# S7CAS-PLEIADES-CARTE-MERE_P06_MOTOR.net
KiCad netlist of a schematic drawn in Altium Designer
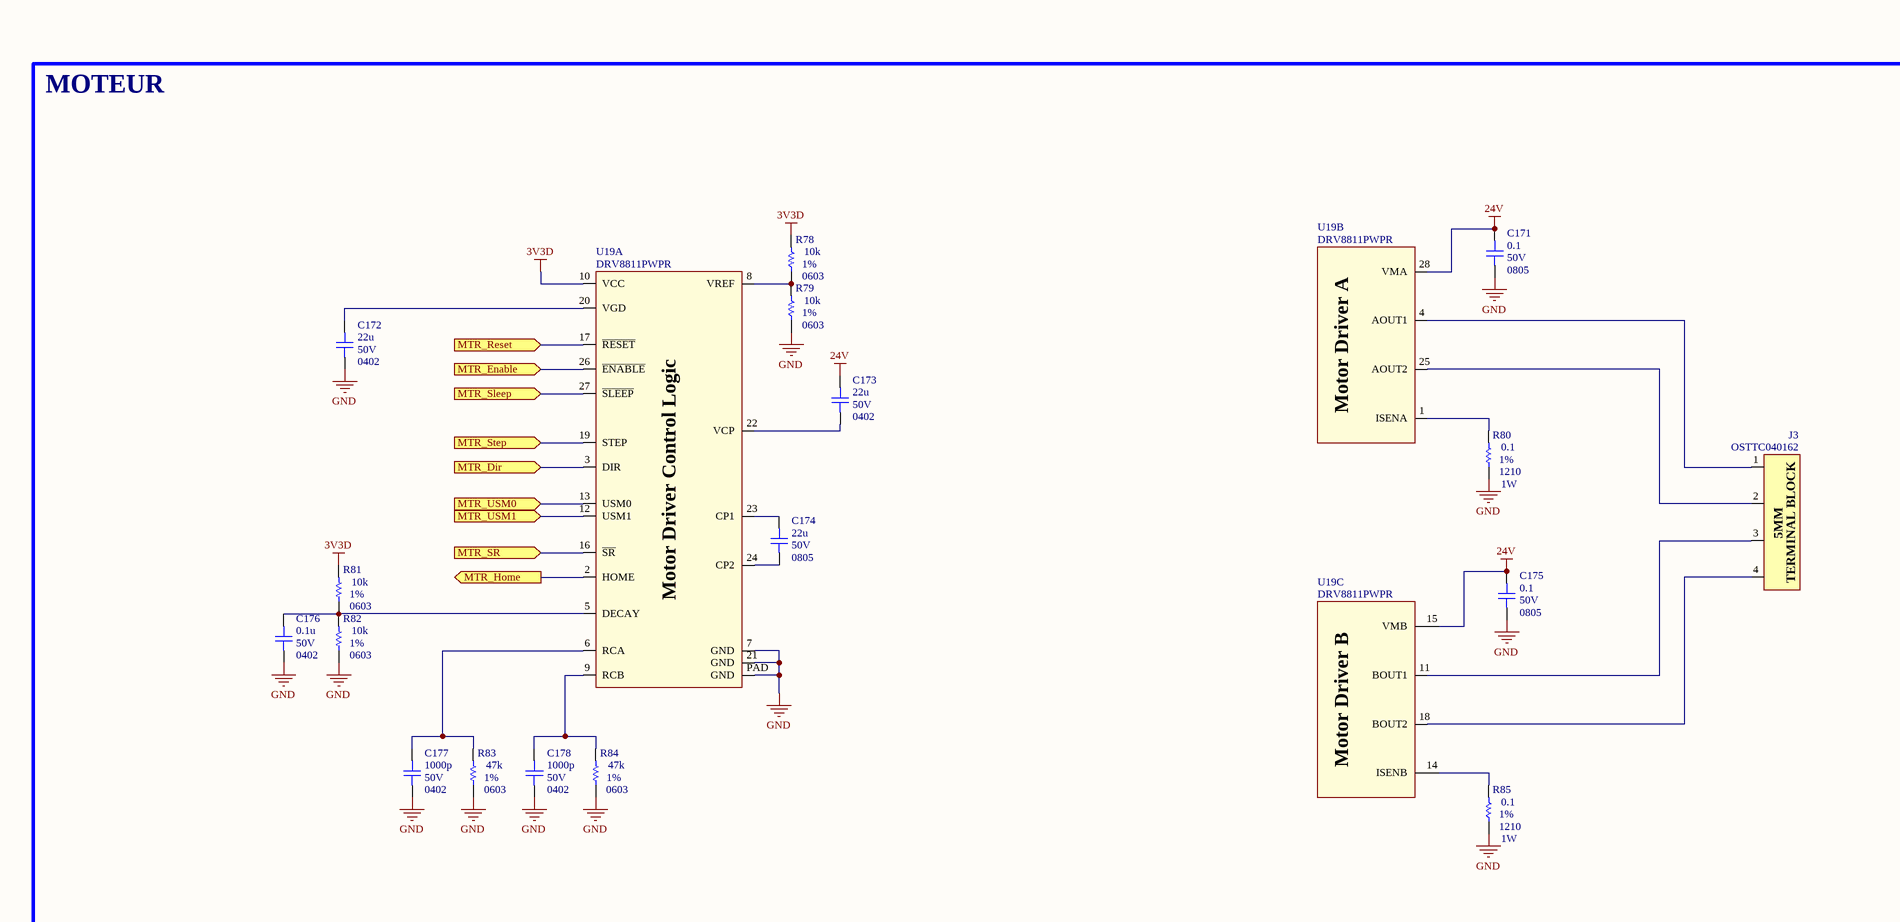
[diagram p0: S7CAS-PLEIADES-CARTE-MERE_P06_MOTOR.SCHDOC, top left]
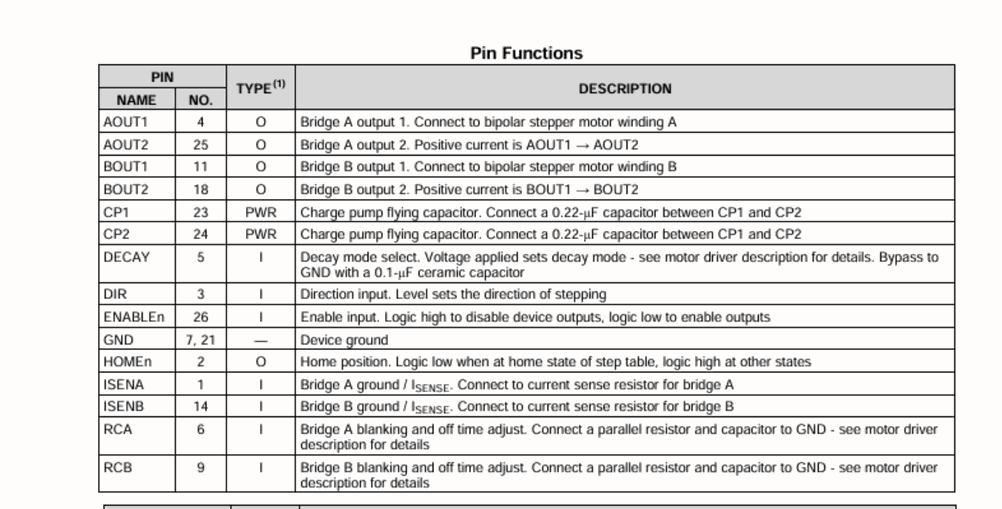
[diagram p1: S7CAS-PLEIADES-CARTE-MERE_P06_MOTOR.SCHDOC, top right]
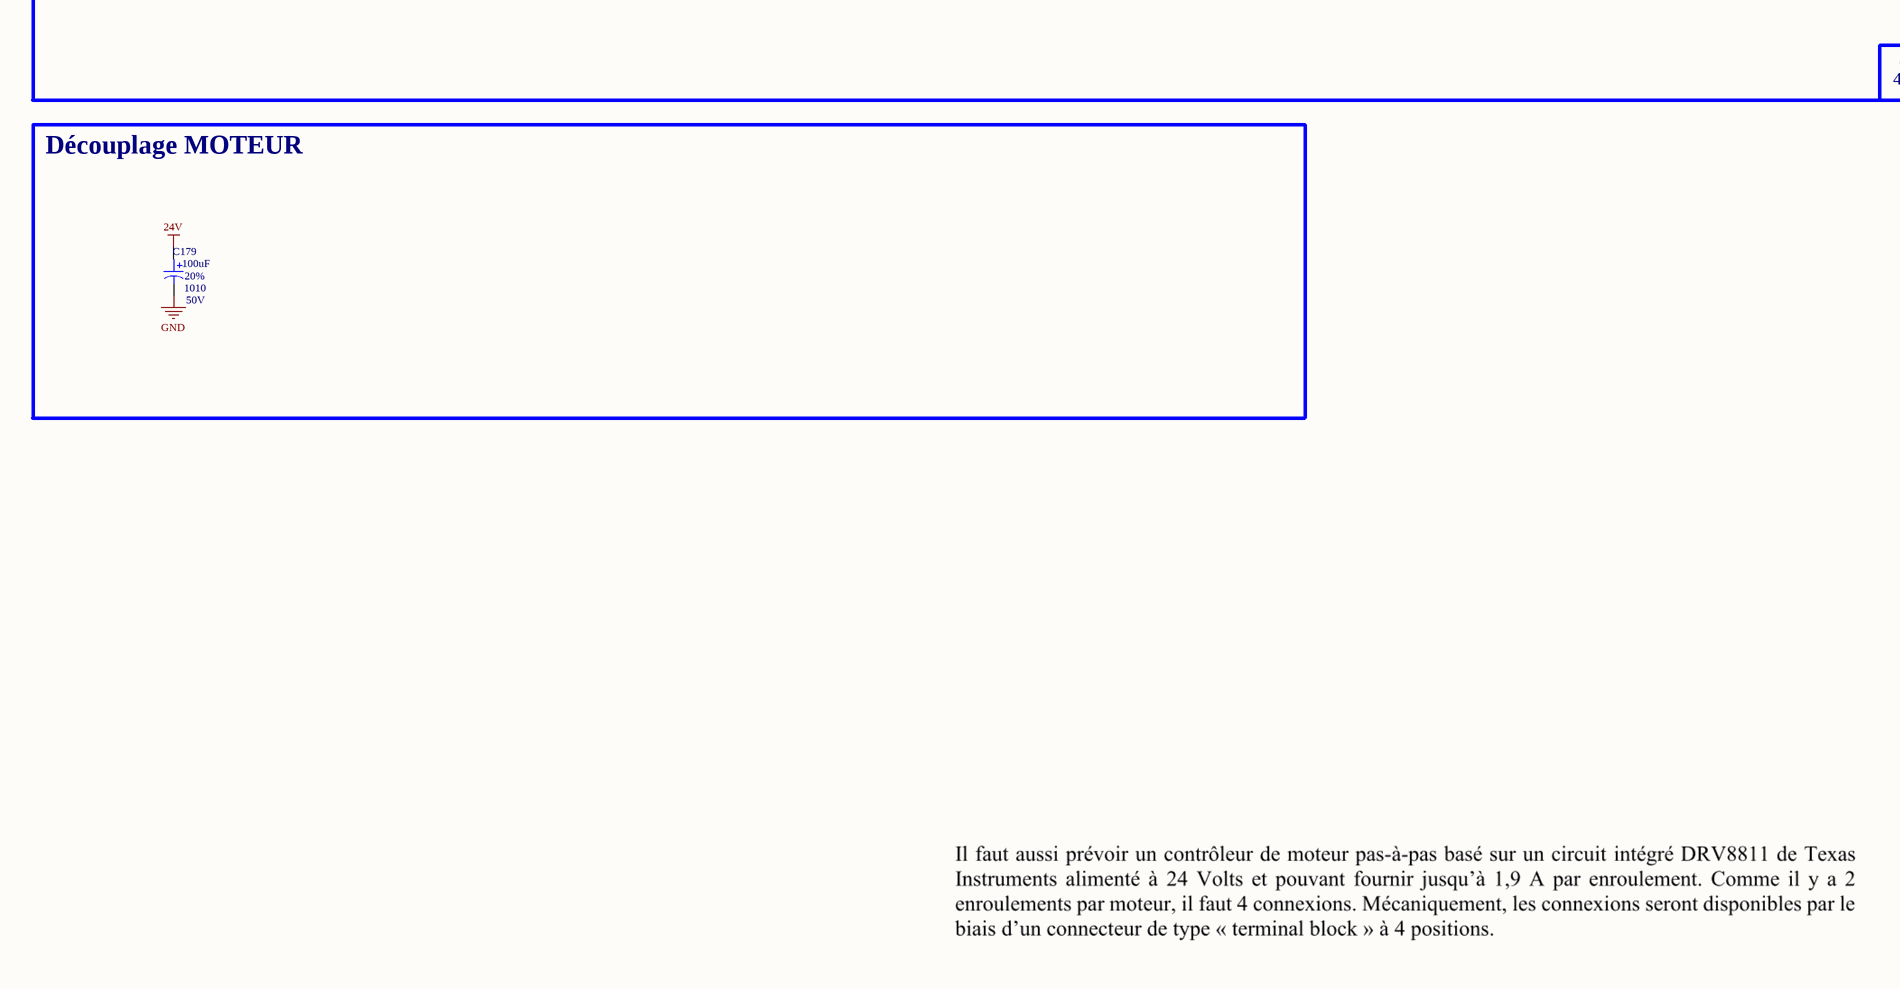
[diagram p2: S7CAS-PLEIADES-CARTE-MERE_P06_MOTOR.SCHDOC, bottom left]
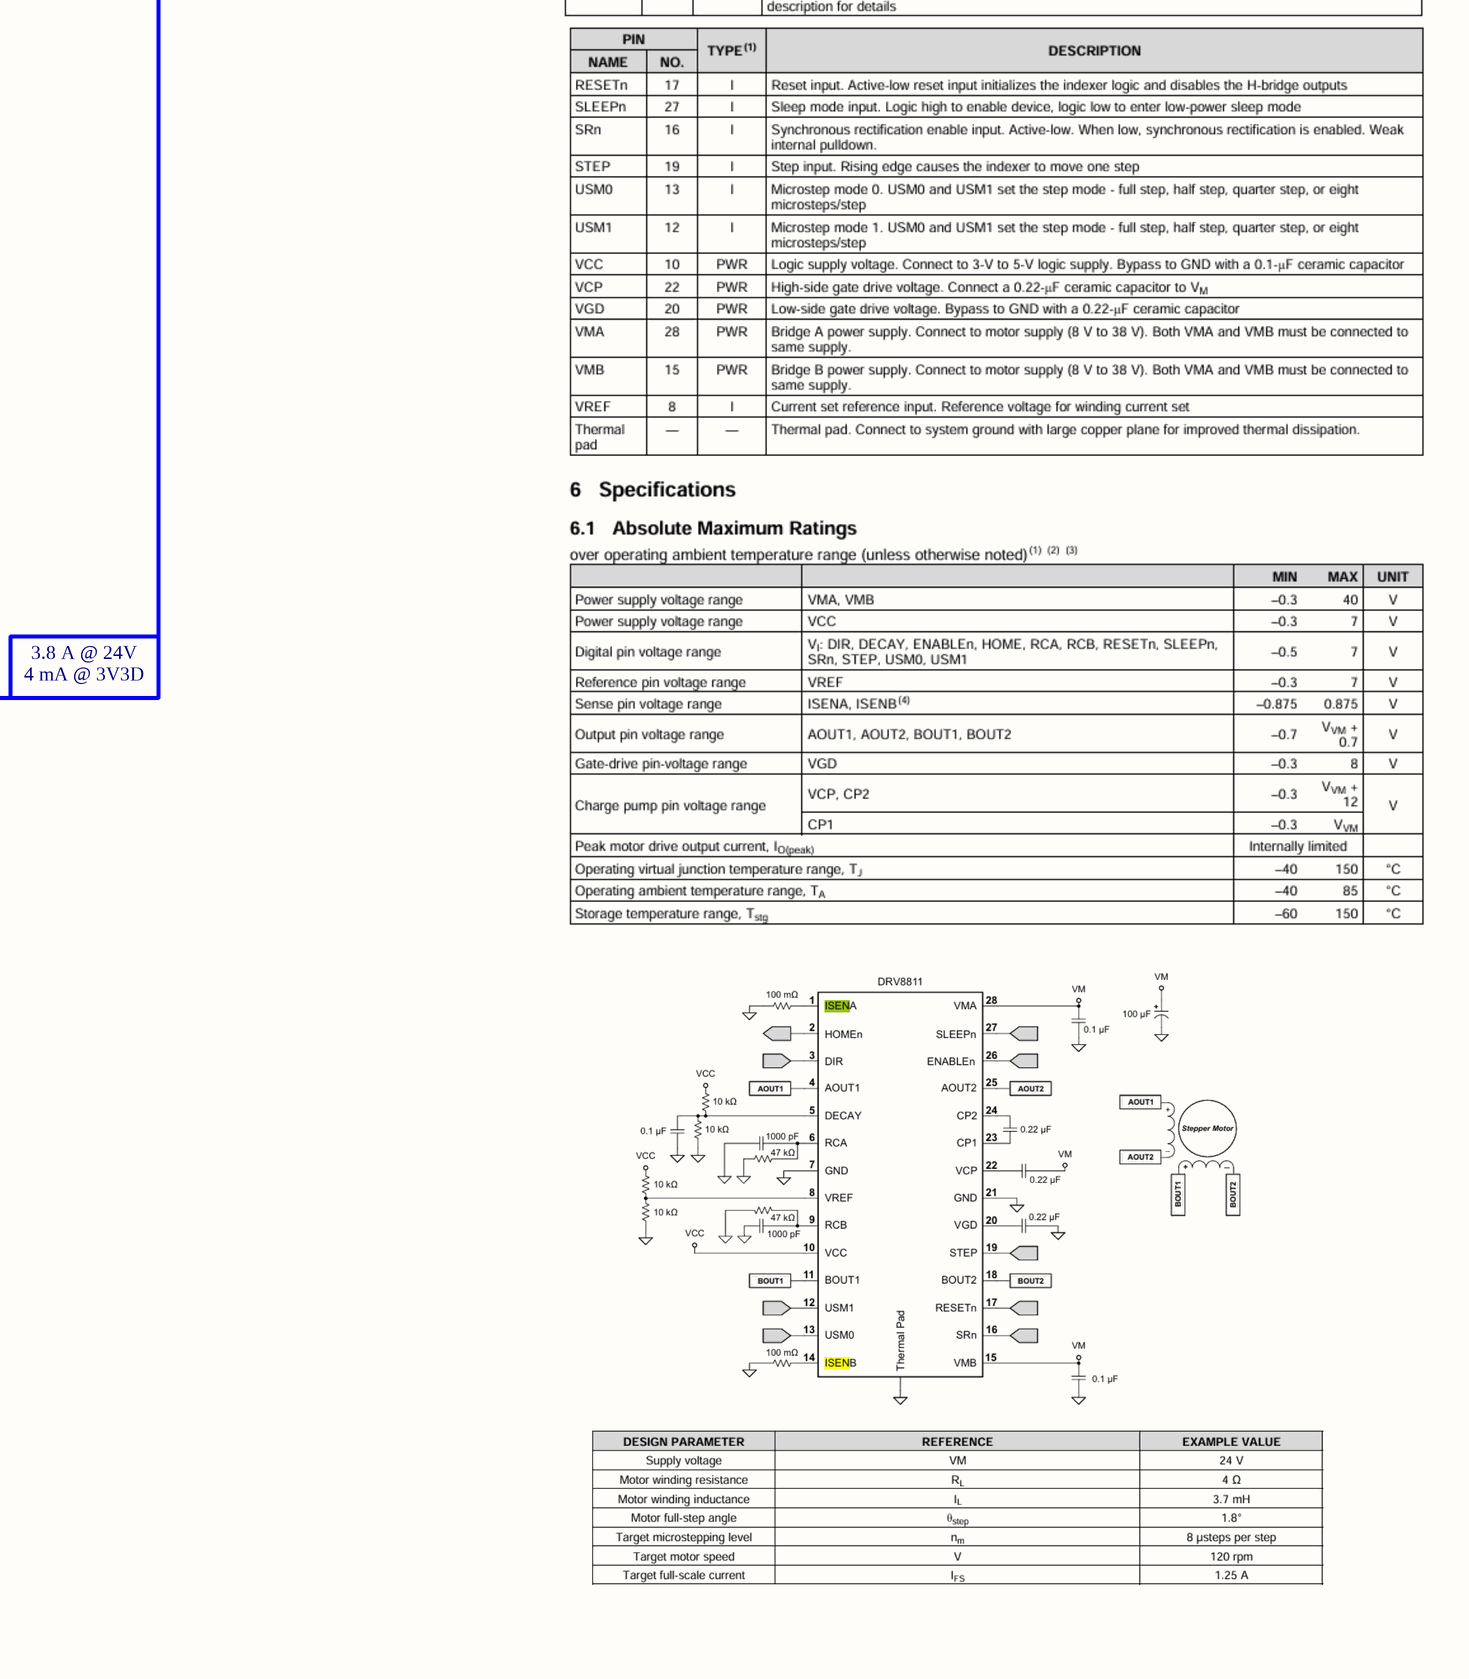
[diagram p3: S7CAS-PLEIADES-CARTE-MERE_P06_MOTOR.SCHDOC, bottom right]

(export (version "E")
  (design (tool "Eeschema 10.0.6"))
  (components
    (comp (ref "C171")
      (value "0.1")
      (footprint "CAP_0805")
      (description "CAP - 0805")
      (fields
        (field (name "VOLTAGE") "50V")
        (field (name "PACKAGE") "0805")
        (field (name "CREATEDBY") "Jonathan Bouchard")
      )
      (libsource (lib "s7cas_lib2023") (part "CAP - 0805"))
    )
    (comp (ref "C172")
      (value "22u")
      (footprint "CAP_0402")
      (description "CAP - 0402")
      (fields
        (field (name "VOLTAGE") "50V")
        (field (name "PACKAGE") "0402")
        (field (name "CREATEDBY") "Jonathan Bouchard")
      )
      (libsource (lib "s7cas_lib2023") (part "CAP - 0402"))
    )
    (comp (ref "C173")
      (value "22u")
      (footprint "CAP_0402")
      (description "CAP - 0402")
      (fields
        (field (name "VOLTAGE") "50V")
        (field (name "PACKAGE") "0402")
        (field (name "CREATEDBY") "Jonathan Bouchard")
      )
      (libsource (lib "s7cas_lib2023") (part "CAP - 0402"))
    )
    (comp (ref "C174")
      (value "22u")
      (footprint "CAP_0805")
      (description "CAP - 0805")
      (fields
        (field (name "VOLTAGE") "50V")
        (field (name "PACKAGE") "0805")
        (field (name "CREATEDBY") "Jonathan Bouchard")
      )
      (libsource (lib "s7cas_lib2023") (part "CAP - 0805"))
    )
    (comp (ref "C175")
      (value "0.1")
      (footprint "CAP_0805")
      (description "CAP - 0805")
      (fields
        (field (name "VOLTAGE") "50V")
        (field (name "PACKAGE") "0805")
        (field (name "CREATEDBY") "Jonathan Bouchard")
      )
      (libsource (lib "s7cas_lib2023") (part "CAP - 0805"))
    )
    (comp (ref "C176")
      (value "0.1u")
      (footprint "CAP_0402")
      (description "CAP - 0402")
      (fields
        (field (name "VOLTAGE") "50V")
        (field (name "PACKAGE") "0402")
        (field (name "CREATEDBY") "Jonathan Bouchard")
      )
      (libsource (lib "s7cas_lib2023") (part "CAP - 0402"))
    )
    (comp (ref "C177")
      (value "1000p")
      (footprint "CAP_0402")
      (description "CAP - 0402")
      (fields
        (field (name "VOLTAGE") "50V")
        (field (name "PACKAGE") "0402")
        (field (name "CREATEDBY") "Jonathan Bouchard")
      )
      (libsource (lib "s7cas_lib2023") (part "CAP - 0402"))
    )
    (comp (ref "C178")
      (value "1000p")
      (footprint "CAP_0402")
      (description "CAP - 0402")
      (fields
        (field (name "VOLTAGE") "50V")
        (field (name "PACKAGE") "0402")
        (field (name "CREATEDBY") "Jonathan Bouchard")
      )
      (libsource (lib "s7cas_lib2023") (part "CAP - 0402"))
    )
    (comp (ref "C179")
      (value "100uF")
      (footprint "CAP_ALU_1010_vishay")
      (description "CAP - ALU 100uF 20% 50V - 1010")
      (fields
        (field (name "MFG") "Vishay Dale")
        (field (name "MFG PART NUMBER") "MAL215099101E3")
        (field (name "VOLTAGE") "50V")
        (field (name "PACKAGE") "1010")
        (field (name "PRECISION") "20%")
        (field (name "CREATEDBY") "Jonathan Bouchard")
      )
      (libsource (lib "s7cas_lib2023") (part "CAP_ALU_MAL215099101E3"))
    )
    (comp (ref "J3")
      (value "OSTTC040162")
      (footprint "CONN_TERMINAL_OSTTA040161")
      (description "CONN -  TERMINAL BLOCK 4POS 5MM - TH")
      (fields (field (name "MFG") "On Shore Technology Inc.") (field (name "CREATEDBY") "Jonathan Bouchard"))
      (libsource (lib "s7cas_lib2023") (part "CONN_TERMINAL_OSTTC040162"))
    )
    (comp (ref "R78")
      (value "10k")
      (footprint "RES_0603")
      (description "RES - 0603")
      (fields
        (field (name "PACKAGE") "0603")
        (field (name "PRECISION") "1%")
        (field (name "CREATEDBY") "Jonathan Bouchard")
      )
      (libsource (lib "s7cas_lib2023") (part "RES - 0603"))
    )
    (comp (ref "R79")
      (value "10k")
      (footprint "RES_0603")
      (description "RES - 0603")
      (fields
        (field (name "PACKAGE") "0603")
        (field (name "PRECISION") "1%")
        (field (name "CREATEDBY") "Jonathan Bouchard")
      )
      (libsource (lib "s7cas_lib2023") (part "RES - 0603"))
    )
    (comp (ref "R80")
      (value "0.1")
      (footprint "RES_1210")
      (description "RES - 1210")
      (fields
        (field (name "POWER") "1W")
        (field (name "PACKAGE") "1210")
        (field (name "PRECISION") "1%")
        (field (name "CREATEDBY") "Jonathan Bouchard")
      )
      (libsource (lib "s7cas_lib2023") (part "RES - 1210"))
    )
    (comp (ref "R81")
      (value "10k")
      (footprint "RES_0603")
      (description "RES - 0603")
      (fields
        (field (name "PACKAGE") "0603")
        (field (name "PRECISION") "1%")
        (field (name "CREATEDBY") "Jonathan Bouchard")
      )
      (libsource (lib "s7cas_lib2023") (part "RES - 0603"))
    )
    (comp (ref "R82")
      (value "10k")
      (footprint "RES_0603")
      (description "RES - 0603")
      (fields
        (field (name "PACKAGE") "0603")
        (field (name "PRECISION") "1%")
        (field (name "CREATEDBY") "Jonathan Bouchard")
      )
      (libsource (lib "s7cas_lib2023") (part "RES - 0603"))
    )
    (comp (ref "R83")
      (value "47k")
      (footprint "RES_0603")
      (description "RES - 0603")
      (fields
        (field (name "PACKAGE") "0603")
        (field (name "PRECISION") "1%")
        (field (name "CREATEDBY") "Jonathan Bouchard")
      )
      (libsource (lib "s7cas_lib2023") (part "RES - 0603"))
    )
    (comp (ref "R84")
      (value "47k")
      (footprint "RES_0603")
      (description "RES - 0603")
      (fields
        (field (name "PACKAGE") "0603")
        (field (name "PRECISION") "1%")
        (field (name "CREATEDBY") "Jonathan Bouchard")
      )
      (libsource (lib "s7cas_lib2023") (part "RES - 0603"))
    )
    (comp (ref "R85")
      (value "0.1")
      (footprint "RES_1210")
      (description "RES - 1210")
      (fields
        (field (name "POWER") "1W")
        (field (name "PACKAGE") "1210")
        (field (name "PRECISION") "1%")
        (field (name "CREATEDBY") "Jonathan Bouchard")
      )
      (libsource (lib "s7cas_lib2023") (part "RES - 1210"))
    )
    (comp (ref "U19")
      (value "DRV8811PWPR")
      (footprint "POW_MOTOR_DRV8811PWPR")
      (description "POW - STEPPER MOTOR DRIVER - SOP-28")
      (fields
        (field (name "VOLTAGE") "3 V ~ 5.5 V / 8 V ~ 38 V")
        (field (name "MFG") "Texas Instrument")
        (field (name "CREATEDBY") "Jonathan Bouchard")
      )
      (libsource (lib "s7cas_lib2023") (part "POW_MOTOR_DRV8811PWPR"))
    )
  )
  (nets
    (net (code "1") (name "/MTR_Dir") (class "Default")
      (node (ref "U19") (pin "3") (pinfunction "DIR_3") (pintype "passive"))
    )
    (net (code "2") (name "/MTR_Enable") (class "Default")
      (node (ref "U19") (pin "26") (pinfunction "~{ENABLE}_26") (pintype "passive"))
    )
    (net (code "3") (name "/MTR_Home") (class "Default")
      (node (ref "U19") (pin "2") (pinfunction "HOME_2") (pintype "passive"))
    )
    (net (code "4") (name "/MTR_Reset") (class "Default")
      (node (ref "U19") (pin "17") (pinfunction "~{RESET}_17") (pintype "passive"))
    )
    (net (code "5") (name "/MTR_SR") (class "Default")
      (node (ref "U19") (pin "16") (pinfunction "~{SR}_16") (pintype "passive"))
    )
    (net (code "6") (name "/MTR_Sleep") (class "Default")
      (node (ref "U19") (pin "27") (pinfunction "~{SLEEP}_27") (pintype "passive"))
    )
    (net (code "7") (name "/MTR_Step") (class "Default")
      (node (ref "U19") (pin "19") (pinfunction "STEP_19") (pintype "passive"))
    )
    (net (code "8") (name "/MTR_USM0") (class "Default")
      (node (ref "U19") (pin "13") (pinfunction "USM0_13") (pintype "passive"))
    )
    (net (code "9") (name "/MTR_USM1") (class "Default")
      (node (ref "U19") (pin "12") (pinfunction "USM1_12") (pintype "passive"))
    )
    (net (code "10") (name "3V3D") (class "Default")
      (node (ref "R78") (pin "2") (pinfunction "2_2") (pintype "passive"))
      (node (ref "R81") (pin "2") (pinfunction "2_2") (pintype "passive"))
      (node (ref "U19") (pin "10") (pinfunction "VCC_10") (pintype "passive"))
    )
    (net (code "11") (name "24V") (class "Default")
      (node (ref "C171") (pin "2") (pinfunction "2_2") (pintype "passive"))
      (node (ref "C173") (pin "2") (pinfunction "2_2") (pintype "passive"))
      (node (ref "C175") (pin "2") (pinfunction "2_2") (pintype "passive"))
      (node (ref "C179") (pin "1") (pinfunction "1_1") (pintype "passive"))
      (node (ref "U19") (pin "15") (pinfunction "VMB_15") (pintype "passive"))
      (node (ref "U19") (pin "28") (pinfunction "VMA_28") (pintype "passive"))
    )
    (net (code "12") (name "GND") (class "Default")
      (node (ref "C171") (pin "1") (pinfunction "1_1") (pintype "passive"))
      (node (ref "C172") (pin "1") (pinfunction "1_1") (pintype "passive"))
      (node (ref "C175") (pin "1") (pinfunction "1_1") (pintype "passive"))
      (node (ref "C176") (pin "1") (pinfunction "1_1") (pintype "passive"))
      (node (ref "C177") (pin "1") (pinfunction "1_1") (pintype "passive"))
      (node (ref "C178") (pin "1") (pinfunction "1_1") (pintype "passive"))
      (node (ref "C179") (pin "2") (pinfunction "2_2") (pintype "passive"))
      (node (ref "R79") (pin "1") (pinfunction "1_1") (pintype "passive"))
      (node (ref "R80") (pin "1") (pinfunction "1_1") (pintype "passive"))
      (node (ref "R82") (pin "1") (pinfunction "1_1") (pintype "passive"))
      (node (ref "R83") (pin "1") (pinfunction "1_1") (pintype "passive"))
      (node (ref "R84") (pin "1") (pinfunction "1_1") (pintype "passive"))
      (node (ref "R85") (pin "1") (pinfunction "1_1") (pintype "passive"))
      (node (ref "U19") (pin "21") (pinfunction "GND_21") (pintype "passive"))
      (node (ref "U19") (pin "7") (pinfunction "GND_7") (pintype "passive"))
      (node (ref "U19") (pin "PAD") (pinfunction "GND_PAD") (pintype "passive"))
    )
    (net (code "13") (name "Net-(U19A-CP1)") (class "Default")
      (node (ref "C174") (pin "2") (pinfunction "2_2") (pintype "passive"))
      (node (ref "U19") (pin "23") (pinfunction "CP1_23") (pintype "passive"))
    )
    (net (code "14") (name "Net-(U19A-CP2)") (class "Default")
      (node (ref "C174") (pin "1") (pinfunction "1_1") (pintype "passive"))
      (node (ref "U19") (pin "24") (pinfunction "CP2_24") (pintype "passive"))
    )
    (net (code "15") (name "Net-(U19A-DECAY)") (class "Default")
      (node (ref "C176") (pin "2") (pinfunction "2_2") (pintype "passive"))
      (node (ref "R81") (pin "1") (pinfunction "1_1") (pintype "passive"))
      (node (ref "R82") (pin "2") (pinfunction "2_2") (pintype "passive"))
      (node (ref "U19") (pin "5") (pinfunction "DECAY_5") (pintype "passive"))
    )
    (net (code "16") (name "Net-(U19A-RCA)") (class "Default")
      (node (ref "C177") (pin "2") (pinfunction "2_2") (pintype "passive"))
      (node (ref "R83") (pin "2") (pinfunction "2_2") (pintype "passive"))
      (node (ref "U19") (pin "6") (pinfunction "RCA_6") (pintype "passive"))
    )
    (net (code "17") (name "Net-(U19A-RCB)") (class "Default")
      (node (ref "C178") (pin "2") (pinfunction "2_2") (pintype "passive"))
      (node (ref "R84") (pin "2") (pinfunction "2_2") (pintype "passive"))
      (node (ref "U19") (pin "9") (pinfunction "RCB_9") (pintype "passive"))
    )
    (net (code "18") (name "Net-(U19A-VCP)") (class "Default")
      (node (ref "C173") (pin "1") (pinfunction "1_1") (pintype "passive"))
      (node (ref "U19") (pin "22") (pinfunction "VCP_22") (pintype "passive"))
    )
    (net (code "19") (name "Net-(U19A-VGD)") (class "Default")
      (node (ref "C172") (pin "2") (pinfunction "2_2") (pintype "passive"))
      (node (ref "U19") (pin "20") (pinfunction "VGD_20") (pintype "passive"))
    )
    (net (code "20") (name "Net-(U19A-VREF)") (class "Default")
      (node (ref "R78") (pin "1") (pinfunction "1_1") (pintype "passive"))
      (node (ref "R79") (pin "2") (pinfunction "2_2") (pintype "passive"))
      (node (ref "U19") (pin "8") (pinfunction "VREF_8") (pintype "passive"))
    )
    (net (code "21") (name "Net-(U19B-AOUT1)") (class "Default")
      (node (ref "J3") (pin "1") (pinfunction "1_1") (pintype "passive"))
      (node (ref "U19") (pin "4") (pinfunction "AOUT1_4") (pintype "passive"))
    )
    (net (code "22") (name "Net-(U19B-AOUT2)") (class "Default")
      (node (ref "J3") (pin "2") (pinfunction "2_2") (pintype "passive"))
      (node (ref "U19") (pin "25") (pinfunction "AOUT2_25") (pintype "passive"))
    )
    (net (code "23") (name "Net-(U19B-ISENA)") (class "Default")
      (node (ref "R80") (pin "2") (pinfunction "2_2") (pintype "passive"))
      (node (ref "U19") (pin "1") (pinfunction "ISENA_1") (pintype "passive"))
    )
    (net (code "24") (name "Net-(U19C-BOUT1)") (class "Default")
      (node (ref "J3") (pin "3") (pinfunction "3_3") (pintype "passive"))
      (node (ref "U19") (pin "11") (pinfunction "BOUT1_11") (pintype "passive"))
    )
    (net (code "25") (name "Net-(U19C-BOUT2)") (class "Default")
      (node (ref "J3") (pin "4") (pinfunction "4_4") (pintype "passive"))
      (node (ref "U19") (pin "18") (pinfunction "BOUT2_18") (pintype "passive"))
    )
    (net (code "26") (name "Net-(U19C-ISENB)") (class "Default")
      (node (ref "R85") (pin "2") (pinfunction "2_2") (pintype "passive"))
      (node (ref "U19") (pin "14") (pinfunction "ISENB_14") (pintype "passive"))
    )
  )
)
